# additional_leds.net
KiCad netlist of a schematic drawn in Altium Designer
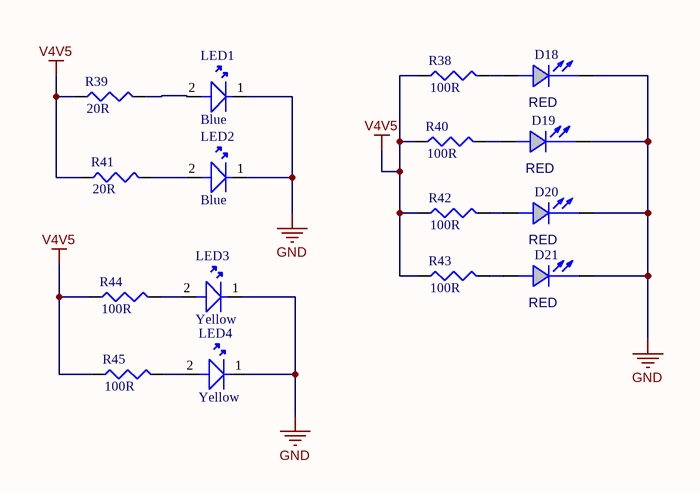
[diagram p0: additional_leds.SchDoc]

(export (version "E")
  (design (tool "Eeschema 10.0.6"))
  (components
    (comp (ref "D18")
      (value "LED-0603")
      (footprint "LEDC1608X40N")
      (fields (field (name "COLOUR") "RED"))
      (libsource (lib "Diamond") (part "LED-0603"))
    )
    (comp (ref "D19")
      (value "LED-0603")
      (footprint "LEDC1608X40N")
      (fields (field (name "COLOUR") "RED"))
      (libsource (lib "Diamond") (part "LED-0603"))
    )
    (comp (ref "D20")
      (value "LED-0603")
      (footprint "LEDC1608X40N")
      (fields (field (name "COLOUR") "RED"))
      (libsource (lib "Diamond") (part "LED-0603"))
    )
    (comp (ref "D21")
      (value "LED-0603")
      (footprint "LEDC1608X40N")
      (fields (field (name "COLOUR") "RED"))
      (libsource (lib "Diamond") (part "LED-0603"))
    )
    (comp (ref "LED1")
      (value "Blue")
      (footprint "Type 3mm")
      (description "THT LED round mono-color waterclear, WL-TMRW , Blue")
      (fields
        (field (name "PARTNO") "151033BS03000")
        (field (name "MANUFACTURER") "Würth Elektronik eiSos GmbH")
        (field (name "CREATED BY") "Christin Otto")
      )
      (libsource (lib "ALTIUM-WL-TMRW-rev15a") (part "WL-TMRW, Type 3mm, 151033BS03000"))
    )
    (comp (ref "LED2")
      (value "Blue")
      (footprint "Type 3mm")
      (description "THT LED round mono-color waterclear, WL-TMRW , Blue")
      (fields
        (field (name "PARTNO") "151033BS03000")
        (field (name "MANUFACTURER") "Würth Elektronik eiSos GmbH")
        (field (name "CREATED BY") "Christin Otto")
      )
      (libsource (lib "ALTIUM-WL-TMRW-rev15a") (part "WL-TMRW, Type 3mm, 151033BS03000"))
    )
    (comp (ref "LED3")
      (value "Yellow")
      (footprint "Type 5mm")
      (description "THT LED round mono-color waterclear, WL-TMRW ,Blue")
      (fields
        (field (name "PARTNO") "151053BS04500")
        (field (name "MANUFACTURER") "Würth Elektronik eiSos GmbH")
        (field (name "CREATED BY") "Christin Otto")
      )
      (libsource (lib "ALTIUM-WL-TMRW-rev15a") (part "WL-TMRW, Type 5mm, 151053BS04500"))
    )
    (comp (ref "LED4")
      (value "Yellow")
      (footprint "Type 5mm")
      (description "THT LED round mono-color waterclear, WL-TMRW ,Blue")
      (fields
        (field (name "PARTNO") "151053BS04500")
        (field (name "MANUFACTURER") "Würth Elektronik eiSos GmbH")
        (field (name "CREATED BY") "Christin Otto")
      )
      (libsource (lib "ALTIUM-WL-TMRW-rev15a") (part "WL-TMRW, Type 5mm, 151053BS04500"))
    )
    (comp (ref "R38")
      (value "100R")
      (footprint "R0805")
      (description "R0805")
      (fields (field (name "PUBLISHER") "Firmwave Limited"))
      (libsource (lib "Diamond") (part "R0805"))
    )
    (comp (ref "R39")
      (value "20R")
      (footprint "R0805")
      (description "R0805")
      (fields (field (name "PUBLISHER") "Firmwave Limited"))
      (libsource (lib "Diamond") (part "R0805"))
    )
    (comp (ref "R40")
      (value "100R")
      (footprint "R0805")
      (description "R0805")
      (fields (field (name "PUBLISHER") "Firmwave Limited"))
      (libsource (lib "Diamond") (part "R0805"))
    )
    (comp (ref "R41")
      (value "20R")
      (footprint "R0805")
      (description "R0805")
      (fields (field (name "PUBLISHER") "Firmwave Limited"))
      (libsource (lib "Diamond") (part "R0805"))
    )
    (comp (ref "R42")
      (value "100R")
      (footprint "R0805")
      (description "R0805")
      (fields (field (name "PUBLISHER") "Firmwave Limited"))
      (libsource (lib "Diamond") (part "R0805"))
    )
    (comp (ref "R43")
      (value "100R")
      (footprint "R0805")
      (description "R0805")
      (fields (field (name "PUBLISHER") "Firmwave Limited"))
      (libsource (lib "Diamond") (part "R0805"))
    )
    (comp (ref "R44")
      (value "100R")
      (footprint "R0805")
      (description "R0805")
      (fields (field (name "PUBLISHER") "Firmwave Limited"))
      (libsource (lib "Diamond") (part "R0805"))
    )
    (comp (ref "R45")
      (value "100R")
      (footprint "R0805")
      (description "R0805")
      (fields (field (name "PUBLISHER") "Firmwave Limited"))
      (libsource (lib "Diamond") (part "R0805"))
    )
  )
  (nets
    (net (code "1") (name "GND") (class "Default")
      (node (ref "D18") (pin "1") (pinfunction "CATHODE_1") (pintype "passive"))
      (node (ref "D19") (pin "1") (pinfunction "CATHODE_1") (pintype "passive"))
      (node (ref "D20") (pin "1") (pinfunction "CATHODE_1") (pintype "passive"))
      (node (ref "D21") (pin "1") (pinfunction "CATHODE_1") (pintype "passive"))
      (node (ref "LED1") (pin "1") (pinfunction "K_1") (pintype "passive"))
      (node (ref "LED2") (pin "1") (pinfunction "K_1") (pintype "passive"))
      (node (ref "LED3") (pin "1") (pinfunction "K_1") (pintype "passive"))
      (node (ref "LED4") (pin "1") (pinfunction "K_1") (pintype "passive"))
    )
    (net (code "2") (name "Net-(D18-ANODE)") (class "Default")
      (node (ref "D18") (pin "2") (pinfunction "ANODE_2") (pintype "passive"))
      (node (ref "R38") (pin "2") (pinfunction "2_2") (pintype "passive"))
    )
    (net (code "3") (name "Net-(D19-ANODE)") (class "Default")
      (node (ref "D19") (pin "2") (pinfunction "ANODE_2") (pintype "passive"))
      (node (ref "R40") (pin "2") (pinfunction "2_2") (pintype "passive"))
    )
    (net (code "4") (name "Net-(D20-ANODE)") (class "Default")
      (node (ref "D20") (pin "2") (pinfunction "ANODE_2") (pintype "passive"))
      (node (ref "R42") (pin "2") (pinfunction "2_2") (pintype "passive"))
    )
    (net (code "5") (name "Net-(D21-ANODE)") (class "Default")
      (node (ref "D21") (pin "2") (pinfunction "ANODE_2") (pintype "passive"))
      (node (ref "R43") (pin "2") (pinfunction "2_2") (pintype "passive"))
    )
    (net (code "6") (name "Net-(LED1-A)") (class "Default")
      (node (ref "LED1") (pin "2") (pinfunction "A_2") (pintype "passive"))
      (node (ref "R39") (pin "2") (pinfunction "2_2") (pintype "passive"))
    )
    (net (code "7") (name "Net-(LED2-A)") (class "Default")
      (node (ref "LED2") (pin "2") (pinfunction "A_2") (pintype "passive"))
      (node (ref "R41") (pin "2") (pinfunction "2_2") (pintype "passive"))
    )
    (net (code "8") (name "Net-(LED3-A)") (class "Default")
      (node (ref "LED3") (pin "2") (pinfunction "A_2") (pintype "passive"))
      (node (ref "R44") (pin "2") (pinfunction "2_2") (pintype "passive"))
    )
    (net (code "9") (name "Net-(LED4-A)") (class "Default")
      (node (ref "LED4") (pin "2") (pinfunction "A_2") (pintype "passive"))
      (node (ref "R45") (pin "2") (pinfunction "2_2") (pintype "passive"))
    )
    (net (code "10") (name "V4V5") (class "Default")
      (node (ref "R38") (pin "1") (pinfunction "1_1") (pintype "passive"))
      (node (ref "R39") (pin "1") (pinfunction "1_1") (pintype "passive"))
      (node (ref "R40") (pin "1") (pinfunction "1_1") (pintype "passive"))
      (node (ref "R41") (pin "1") (pinfunction "1_1") (pintype "passive"))
      (node (ref "R42") (pin "1") (pinfunction "1_1") (pintype "passive"))
      (node (ref "R43") (pin "1") (pinfunction "1_1") (pintype "passive"))
      (node (ref "R44") (pin "1") (pinfunction "1_1") (pintype "passive"))
      (node (ref "R45") (pin "1") (pinfunction "1_1") (pintype "passive"))
    )
  )
)
